# HW1_58.net
KiCad netlist of a schematic drawn in EasyEDA
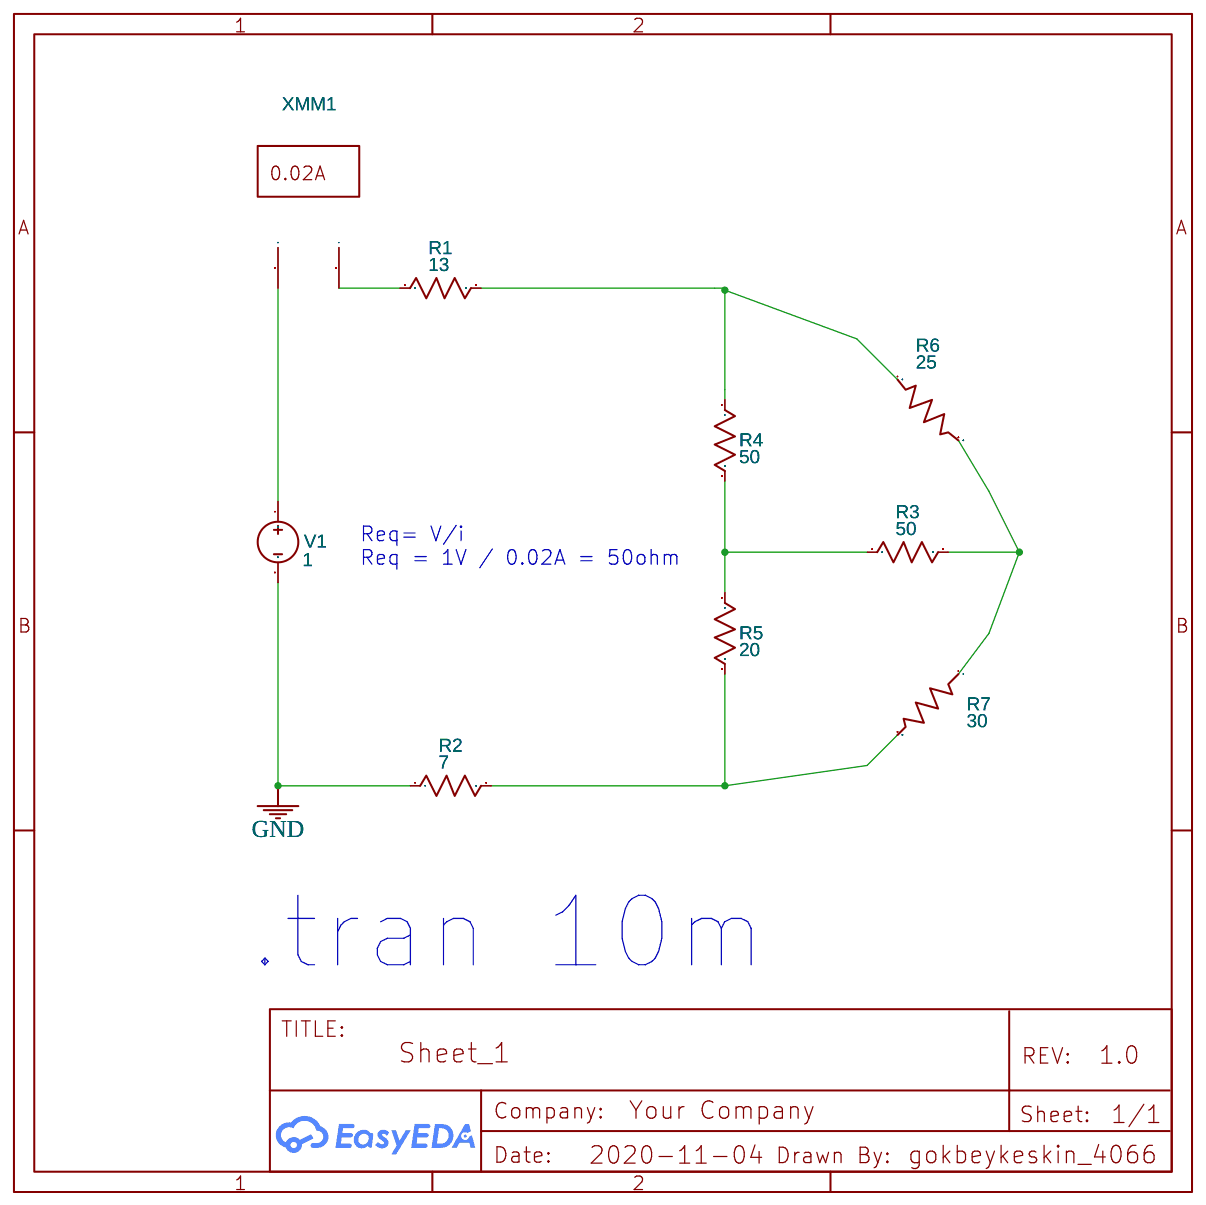
[diagram p0: schematic sheet]

(export (version "E")
  (design (tool "Eeschema 10.0.6"))
  (components
    (comp (ref "R1") (value "13") (libsource (lib "") (part "Resistor_US")))
    (comp (ref "R2") (value "7") (libsource (lib "") (part "Resistor_US")))
    (comp (ref "R3") (value "50") (libsource (lib "") (part "Resistor_US")))
    (comp (ref "R4") (value "50") (libsource (lib "") (part "Resistor_US_1")))
    (comp (ref "R5") (value "20") (libsource (lib "") (part "Resistor_US_1")))
    (comp (ref "R6") (value "25") (libsource (lib "") (part "Resistor_45Degree_US")))
    (comp (ref "R7") (value "30") (libsource (lib "") (part "Resistor_45Degree_US_1")))
    (comp (ref "V1") (value "1") (libsource (lib "") (part "VDC")))
    (comp (ref "XMM1") (value "Multimeter") (libsource (lib "") (part "MULTIMETER")))
  )
  (nets
    (net (code "1") (name "GND") (class "Default")
      (node (ref "R2") (pin "1") (pinfunction "1_1") (pintype "unspecified"))
      (node (ref "V1") (pin "2") (pinfunction "2_2") (pintype "unspecified"))
    )
    (net (code "2") (name "Net-(R1-Pad2)") (class "Default")
      (node (ref "R1") (pin "2") (pinfunction "2_2") (pintype "unspecified"))
      (node (ref "R4") (pin "1") (pinfunction "1_1") (pintype "unspecified"))
      (node (ref "R6") (pin "1") (pinfunction "1_1") (pintype "unspecified"))
    )
    (net (code "3") (name "Net-(R2-Pad2)") (class "Default")
      (node (ref "R2") (pin "2") (pinfunction "2_2") (pintype "unspecified"))
      (node (ref "R5") (pin "2") (pinfunction "2_2") (pintype "unspecified"))
      (node (ref "R7") (pin "2") (pinfunction "2_2") (pintype "unspecified"))
    )
    (net (code "4") (name "Net-(R3-Pad1)") (class "Default")
      (node (ref "R3") (pin "1") (pinfunction "1_1") (pintype "unspecified"))
      (node (ref "R4") (pin "2") (pinfunction "2_2") (pintype "unspecified"))
      (node (ref "R5") (pin "1") (pinfunction "1_1") (pintype "unspecified"))
    )
    (net (code "5") (name "Net-(R3-Pad2)") (class "Default")
      (node (ref "R3") (pin "2") (pinfunction "2_2") (pintype "unspecified"))
      (node (ref "R6") (pin "2") (pinfunction "2_2") (pintype "unspecified"))
      (node (ref "R7") (pin "1") (pinfunction "1_1") (pintype "unspecified"))
    )
    (net (code "6") (name "Net-(XMM1-+)") (class "Default")
      (node (ref "V1") (pin "1") (pinfunction "1_1") (pintype "unspecified"))
      (node (ref "XMM1") (pin "1") (pinfunction "+_1") (pintype "unspecified"))
    )
    (net (code "7") (name "Net-(XMM1-I)") (class "Default")
      (node (ref "R1") (pin "1") (pinfunction "1_1") (pintype "unspecified"))
      (node (ref "XMM1") (pin "2") (pinfunction "I_2") (pintype "unspecified"))
    )
  )
)
